# 3_EVB-A32S1-M_Motor.net
KiCad netlist of a schematic drawn in Altium Designer
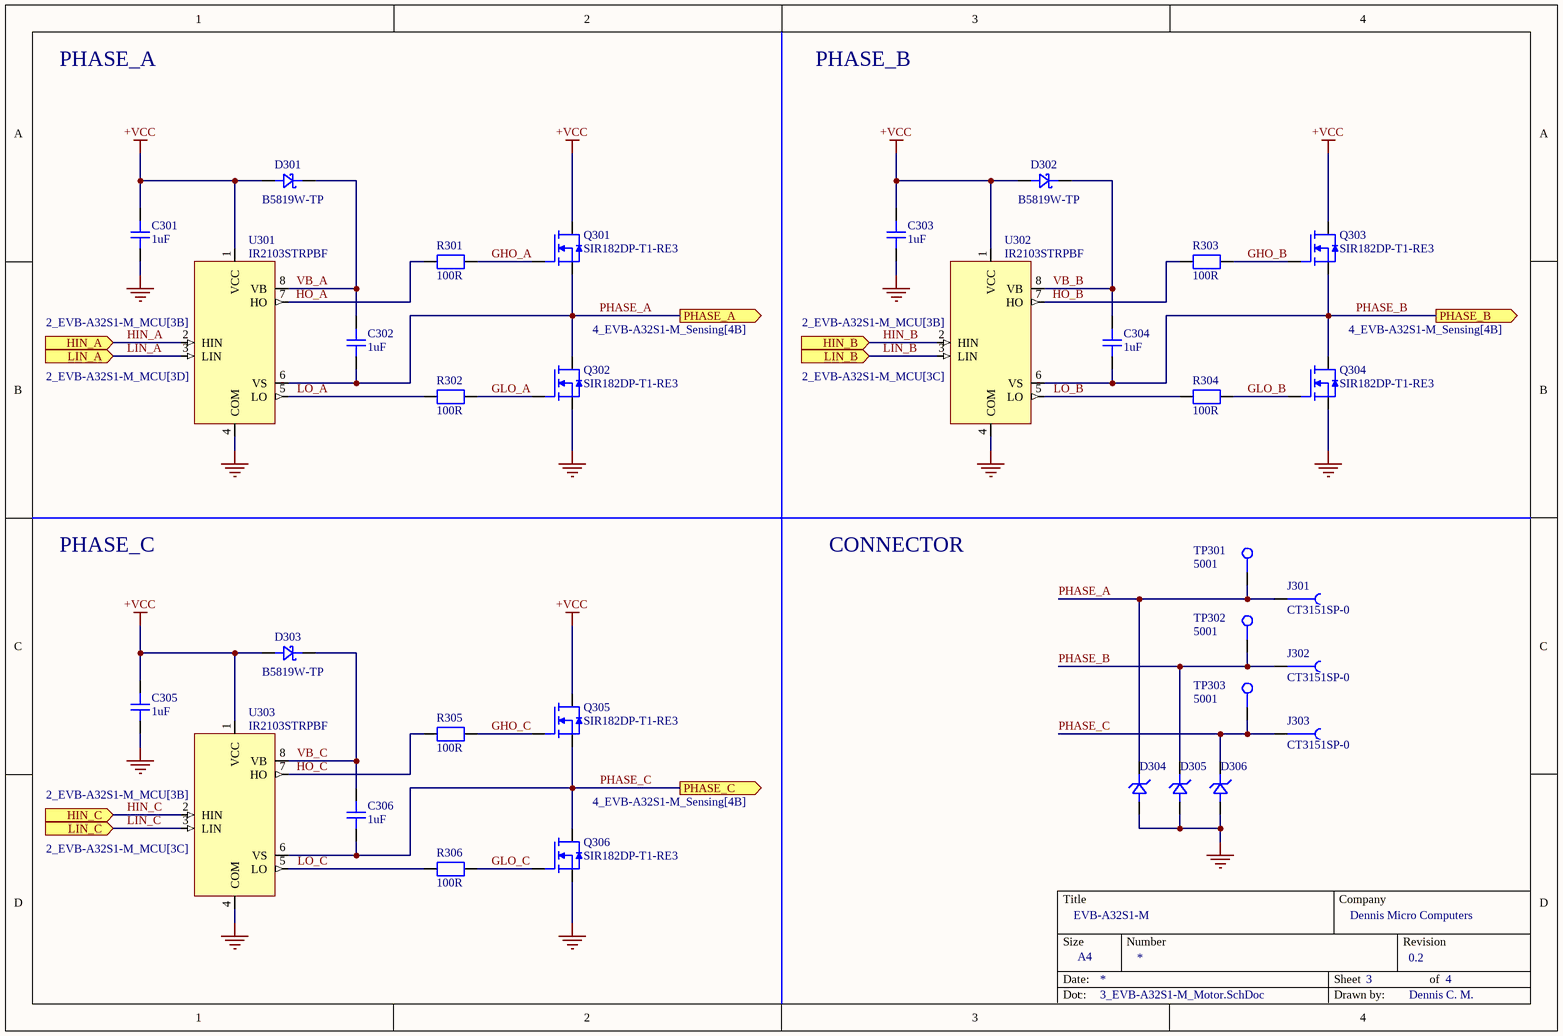
[diagram p0: 3_EVB-A32S1-M_Motor.SchDoc]

(export (version "E")
  (design (tool "Eeschema 10.0.6"))
  (components
    (comp (ref "C301")
      (value "1uF")
      (footprint "C_Yageo_CC_0603_A")
      (description "Multilayer Ceramic Capacitor, 1 uF, 16 V, ± 10%, X7R, 0603 [1608 Metric]")
      (fields (field (name "TOLERANCE") "10%") (field (name "VOLTAGE") "16V"))
      (libsource (lib "Dennis Micro Computers") (part "C"))
    )
    (comp (ref "C302")
      (value "1uF")
      (footprint "C_Yageo_CC_0603_A")
      (description "Multilayer Ceramic Capacitor, 1 uF, 16 V, ± 10%, X7R, 0603 [1608 Metric]")
      (fields (field (name "TOLERANCE") "10%") (field (name "VOLTAGE") "16V"))
      (libsource (lib "Dennis Micro Computers") (part "C"))
    )
    (comp (ref "C303")
      (value "1uF")
      (footprint "C_Yageo_CC_0603_A")
      (description "Multilayer Ceramic Capacitor, 1 uF, 16 V, ± 10%, X7R, 0603 [1608 Metric]")
      (fields (field (name "TOLERANCE") "10%") (field (name "VOLTAGE") "16V"))
      (libsource (lib "Dennis Micro Computers") (part "C"))
    )
    (comp (ref "C304")
      (value "1uF")
      (footprint "C_Yageo_CC_0603_A")
      (description "Multilayer Ceramic Capacitor, 1 uF, 16 V, ± 10%, X7R, 0603 [1608 Metric]")
      (fields (field (name "TOLERANCE") "10%") (field (name "VOLTAGE") "16V"))
      (libsource (lib "Dennis Micro Computers") (part "C"))
    )
    (comp (ref "C305")
      (value "1uF")
      (footprint "C_Yageo_CC_0603_A")
      (description "Multilayer Ceramic Capacitor, 1 uF, 16 V, ± 10%, X7R, 0603 [1608 Metric]")
      (fields (field (name "TOLERANCE") "10%") (field (name "VOLTAGE") "16V"))
      (libsource (lib "Dennis Micro Computers") (part "C"))
    )
    (comp (ref "C306")
      (value "1uF")
      (footprint "C_Yageo_CC_0603_A")
      (description "Multilayer Ceramic Capacitor, 1 uF, 16 V, ± 10%, X7R, 0603 [1608 Metric]")
      (fields (field (name "TOLERANCE") "10%") (field (name "VOLTAGE") "16V"))
      (libsource (lib "Dennis Micro Computers") (part "C"))
    )
    (comp (ref "D301")
      (value "B5819W-TP")
      (footprint "D_Schottky_MCC_SOD-123")
      (description "Rectifier Diode, Schottky, 1 Phase, 1 Element, 1A, 40V V(RRM), Silicon")
      (libsource (lib "Dennis Micro Computers") (part "D_Schottky"))
    )
    (comp (ref "D302")
      (value "B5819W-TP")
      (footprint "D_Schottky_MCC_SOD-123")
      (description "Rectifier Diode, Schottky, 1 Phase, 1 Element, 1A, 40V V(RRM), Silicon")
      (libsource (lib "Dennis Micro Computers") (part "D_Schottky"))
    )
    (comp (ref "D303")
      (value "B5819W-TP")
      (footprint "D_Schottky_MCC_SOD-123")
      (description "Rectifier Diode, Schottky, 1 Phase, 1 Element, 1A, 40V V(RRM), Silicon")
      (libsource (lib "Dennis Micro Computers") (part "D_Schottky"))
    )
    (comp (ref "D304")
      (value "SMBJ15A-13-F")
      (footprint "D_TVS_Uni_Diodes_DO-214AA_B")
      (description "TVS Diode Single Uni-Dir 15V 600W 2-Pin SMB T/R / TVS DIODE 15VWM 24.4VC SMB")
      (libsource (lib "Dennis Micro Computers") (part "D_TVS_Uni"))
    )
    (comp (ref "D305")
      (value "SMBJ15A-13-F")
      (footprint "D_TVS_Uni_Diodes_DO-214AA_B")
      (description "TVS Diode Single Uni-Dir 15V 600W 2-Pin SMB T/R / TVS DIODE 15VWM 24.4VC SMB")
      (libsource (lib "Dennis Micro Computers") (part "D_TVS_Uni"))
    )
    (comp (ref "D306")
      (value "SMBJ15A-13-F")
      (footprint "D_TVS_Uni_Diodes_DO-214AA_B")
      (description "TVS Diode Single Uni-Dir 15V 600W 2-Pin SMB T/R / TVS DIODE 15VWM 24.4VC SMB")
      (libsource (lib "Dennis Micro Computers") (part "D_TVS_Uni"))
    )
    (comp (ref "J301")
      (value "CT3151SP-0")
      (footprint "J_CalTest_CT3151SP-0")
      (description "Conn 4mm Safety Banana Jack F 1 POS Solder RA Thru-Hole 1 Port Bag")
      (libsource (lib "Dennis Micro Computers") (part "J_01x01_Socket"))
    )
    (comp (ref "J302")
      (value "CT3151SP-0")
      (footprint "J_CalTest_CT3151SP-0")
      (description "Conn 4mm Safety Banana Jack F 1 POS Solder RA Thru-Hole 1 Port Bag")
      (libsource (lib "Dennis Micro Computers") (part "J_01x01_Socket"))
    )
    (comp (ref "J303")
      (value "CT3151SP-0")
      (footprint "J_CalTest_CT3151SP-0")
      (description "Conn 4mm Safety Banana Jack F 1 POS Solder RA Thru-Hole 1 Port Bag")
      (libsource (lib "Dennis Micro Computers") (part "J_01x01_Socket"))
    )
    (comp (ref "Q301")
      (value "SIR182DP-T1-RE3")
      (footprint "Q_Vishay_PowerPACK-SO-8-Single")
      (description "TrenchFET Gen IV Power MOSFET N-Channel Single 60V VDS ±20V VGS 60A ID 8-Pin PowerPAK SOIC T/R")
      (libsource (lib "Dennis Micro Computers") (part "Q_NMOS"))
    )
    (comp (ref "Q302")
      (value "SIR182DP-T1-RE3")
      (footprint "Q_Vishay_PowerPACK-SO-8-Single")
      (description "TrenchFET Gen IV Power MOSFET N-Channel Single 60V VDS ±20V VGS 60A ID 8-Pin PowerPAK SOIC T/R")
      (libsource (lib "Dennis Micro Computers") (part "Q_NMOS"))
    )
    (comp (ref "Q303")
      (value "SIR182DP-T1-RE3")
      (footprint "Q_Vishay_PowerPACK-SO-8-Single")
      (description "TrenchFET Gen IV Power MOSFET N-Channel Single 60V VDS ±20V VGS 60A ID 8-Pin PowerPAK SOIC T/R")
      (libsource (lib "Dennis Micro Computers") (part "Q_NMOS"))
    )
    (comp (ref "Q304")
      (value "SIR182DP-T1-RE3")
      (footprint "Q_Vishay_PowerPACK-SO-8-Single")
      (description "TrenchFET Gen IV Power MOSFET N-Channel Single 60V VDS ±20V VGS 60A ID 8-Pin PowerPAK SOIC T/R")
      (libsource (lib "Dennis Micro Computers") (part "Q_NMOS"))
    )
    (comp (ref "Q305")
      (value "SIR182DP-T1-RE3")
      (footprint "Q_Vishay_PowerPACK-SO-8-Single")
      (description "TrenchFET Gen IV Power MOSFET N-Channel Single 60V VDS ±20V VGS 60A ID 8-Pin PowerPAK SOIC T/R")
      (libsource (lib "Dennis Micro Computers") (part "Q_NMOS"))
    )
    (comp (ref "Q306")
      (value "SIR182DP-T1-RE3")
      (footprint "Q_Vishay_PowerPACK-SO-8-Single")
      (description "TrenchFET Gen IV Power MOSFET N-Channel Single 60V VDS ±20V VGS 60A ID 8-Pin PowerPAK SOIC T/R")
      (libsource (lib "Dennis Micro Computers") (part "Q_NMOS"))
    )
    (comp (ref "R301")
      (value "100R")
      (footprint "R_Yageo_RCL_1206_A")
      (description "SMD Chip Resistor, 100 Ohm, ± 1%, 250 mW, 1206 [3216 Metric], Thick Film, General Purpose")
      (fields (field (name "TOLERANCE") "1%") (field (name "Comment") "RC1206FR-07100RL"))
      (libsource (lib "Dennis Micro Computers") (part "R"))
    )
    (comp (ref "R302")
      (value "100R")
      (footprint "R_Yageo_RCL_1206_A")
      (description "SMD Chip Resistor, 100 Ohm, ± 1%, 250 mW, 1206 [3216 Metric], Thick Film, General Purpose")
      (fields (field (name "TOLERANCE") "1%") (field (name "Comment") "RC1206FR-07100RL"))
      (libsource (lib "Dennis Micro Computers") (part "R"))
    )
    (comp (ref "R303")
      (value "100R")
      (footprint "R_Yageo_RCL_1206_A")
      (description "SMD Chip Resistor, 100 Ohm, ± 1%, 250 mW, 1206 [3216 Metric], Thick Film, General Purpose")
      (fields (field (name "TOLERANCE") "1%") (field (name "Comment") "RC1206FR-07100RL"))
      (libsource (lib "Dennis Micro Computers") (part "R"))
    )
    (comp (ref "R304")
      (value "100R")
      (footprint "R_Yageo_RCL_1206_A")
      (description "SMD Chip Resistor, 100 Ohm, ± 1%, 250 mW, 1206 [3216 Metric], Thick Film, General Purpose")
      (fields (field (name "TOLERANCE") "1%") (field (name "Comment") "RC1206FR-07100RL"))
      (libsource (lib "Dennis Micro Computers") (part "R"))
    )
    (comp (ref "R305")
      (value "100R")
      (footprint "R_Yageo_RCL_1206_A")
      (description "SMD Chip Resistor, 100 Ohm, ± 1%, 250 mW, 1206 [3216 Metric], Thick Film, General Purpose")
      (fields (field (name "TOLERANCE") "1%") (field (name "Comment") "RC1206FR-07100RL"))
      (libsource (lib "Dennis Micro Computers") (part "R"))
    )
    (comp (ref "R306")
      (value "100R")
      (footprint "R_Yageo_RCL_1206_A")
      (description "SMD Chip Resistor, 100 Ohm, ± 1%, 250 mW, 1206 [3216 Metric], Thick Film, General Purpose")
      (fields (field (name "TOLERANCE") "1%") (field (name "Comment") "RC1206FR-07100RL"))
      (libsource (lib "Dennis Micro Computers") (part "R"))
    )
    (comp (ref "TP301")
      (value "5001")
      (footprint "TP_Keystone_TH")
      (libsource (lib "Dennis Micro Computers") (part "TP"))
    )
    (comp (ref "TP302")
      (value "5001")
      (footprint "TP_Keystone_TH")
      (libsource (lib "Dennis Micro Computers") (part "TP"))
    )
    (comp (ref "TP303")
      (value "5001")
      (footprint "TP_Keystone_TH")
      (libsource (lib "Dennis Micro Computers") (part "TP"))
    )
    (comp (ref "U301")
      (value "IR2103STRPBF")
      (footprint "U_Infineon_8-SOIC_3.9mm")
      (description "600 V half-bridge gate driver IC with shoot through protection, SOIC 8N, RoHS")
      (libsource (lib "Dennis Micro Computers") (part "U_IR2103STRPBF"))
    )
    (comp (ref "U302")
      (value "IR2103STRPBF")
      (footprint "U_Infineon_8-SOIC_3.9mm")
      (description "600 V half-bridge gate driver IC with shoot through protection, SOIC 8N, RoHS")
      (libsource (lib "Dennis Micro Computers") (part "U_IR2103STRPBF"))
    )
    (comp (ref "U303")
      (value "IR2103STRPBF")
      (footprint "U_Infineon_8-SOIC_3.9mm")
      (description "600 V half-bridge gate driver IC with shoot through protection, SOIC 8N, RoHS")
      (libsource (lib "Dennis Micro Computers") (part "U_IR2103STRPBF"))
    )
  )
  (nets
    (net (code "1") (name "+VCC") (class "Default")
      (node (ref "C301") (pin "2") (pinfunction "2_2") (pintype "passive"))
      (node (ref "C303") (pin "2") (pinfunction "2_2") (pintype "passive"))
      (node (ref "C305") (pin "2") (pinfunction "2_2") (pintype "passive"))
      (node (ref "D301") (pin "2") (pinfunction "2_2") (pintype "passive"))
      (node (ref "D302") (pin "2") (pinfunction "2_2") (pintype "passive"))
      (node (ref "D303") (pin "2") (pinfunction "2_2") (pintype "passive"))
      (node (ref "Q301") (pin "1") (pinfunction "D_1") (pintype "passive"))
      (node (ref "Q303") (pin "1") (pinfunction "D_1") (pintype "passive"))
      (node (ref "Q305") (pin "1") (pinfunction "D_1") (pintype "passive"))
      (node (ref "U301") (pin "1") (pinfunction "VCC_1") (pintype "power_in"))
      (node (ref "U302") (pin "1") (pinfunction "VCC_1") (pintype "power_in"))
      (node (ref "U303") (pin "1") (pinfunction "VCC_1") (pintype "power_in"))
    )
    (net (code "2") (name "/GHO_A") (class "Default")
      (node (ref "Q301") (pin "2") (pinfunction "G_2") (pintype "passive"))
      (node (ref "R301") (pin "2") (pinfunction "2_2") (pintype "passive"))
    )
    (net (code "3") (name "/GHO_B") (class "Default")
      (node (ref "Q303") (pin "2") (pinfunction "G_2") (pintype "passive"))
      (node (ref "R303") (pin "2") (pinfunction "2_2") (pintype "passive"))
    )
    (net (code "4") (name "/GHO_C") (class "Default")
      (node (ref "Q305") (pin "2") (pinfunction "G_2") (pintype "passive"))
      (node (ref "R305") (pin "2") (pinfunction "2_2") (pintype "passive"))
    )
    (net (code "5") (name "/GLO_A") (class "Default")
      (node (ref "Q302") (pin "2") (pinfunction "G_2") (pintype "passive"))
      (node (ref "R302") (pin "2") (pinfunction "2_2") (pintype "passive"))
    )
    (net (code "6") (name "/GLO_B") (class "Default")
      (node (ref "Q304") (pin "2") (pinfunction "G_2") (pintype "passive"))
      (node (ref "R304") (pin "2") (pinfunction "2_2") (pintype "passive"))
    )
    (net (code "7") (name "/GLO_C") (class "Default")
      (node (ref "Q306") (pin "2") (pinfunction "G_2") (pintype "passive"))
      (node (ref "R306") (pin "2") (pinfunction "2_2") (pintype "passive"))
    )
    (net (code "8") (name "/HIN_A") (class "Default")
      (node (ref "U301") (pin "2") (pinfunction "HIN_2") (pintype "input"))
    )
    (net (code "9") (name "/HIN_B") (class "Default")
      (node (ref "U302") (pin "2") (pinfunction "HIN_2") (pintype "input"))
    )
    (net (code "10") (name "/HIN_C") (class "Default")
      (node (ref "U303") (pin "2") (pinfunction "HIN_2") (pintype "input"))
    )
    (net (code "11") (name "/HO_A") (class "Default")
      (node (ref "R301") (pin "1") (pinfunction "1_1") (pintype "passive"))
      (node (ref "U301") (pin "7") (pinfunction "HO_7") (pintype "output"))
    )
    (net (code "12") (name "/HO_B") (class "Default")
      (node (ref "R303") (pin "1") (pinfunction "1_1") (pintype "passive"))
      (node (ref "U302") (pin "7") (pinfunction "HO_7") (pintype "output"))
    )
    (net (code "13") (name "/HO_C") (class "Default")
      (node (ref "R305") (pin "1") (pinfunction "1_1") (pintype "passive"))
      (node (ref "U303") (pin "7") (pinfunction "HO_7") (pintype "output"))
    )
    (net (code "14") (name "/LIN_A") (class "Default")
      (node (ref "U301") (pin "3") (pinfunction "LIN_3") (pintype "input"))
    )
    (net (code "15") (name "/LIN_B") (class "Default")
      (node (ref "U302") (pin "3") (pinfunction "LIN_3") (pintype "input"))
    )
    (net (code "16") (name "/LIN_C") (class "Default")
      (node (ref "U303") (pin "3") (pinfunction "LIN_3") (pintype "input"))
    )
    (net (code "17") (name "/LO_A") (class "Default")
      (node (ref "R302") (pin "1") (pinfunction "1_1") (pintype "passive"))
      (node (ref "U301") (pin "5") (pinfunction "LO_5") (pintype "output"))
    )
    (net (code "18") (name "/LO_B") (class "Default")
      (node (ref "R304") (pin "1") (pinfunction "1_1") (pintype "passive"))
      (node (ref "U302") (pin "5") (pinfunction "LO_5") (pintype "output"))
    )
    (net (code "19") (name "/LO_C") (class "Default")
      (node (ref "R306") (pin "1") (pinfunction "1_1") (pintype "passive"))
      (node (ref "U303") (pin "5") (pinfunction "LO_5") (pintype "output"))
    )
    (net (code "20") (name "/PHASE_A") (class "Default")
      (node (ref "C302") (pin "1") (pinfunction "1_1") (pintype "passive"))
      (node (ref "D304") (pin "1") (pinfunction "1_1") (pintype "passive"))
      (node (ref "J301") (pin "1") (pinfunction "1_1") (pintype "passive"))
      (node (ref "Q301") (pin "3") (pinfunction "S_3") (pintype "passive"))
      (node (ref "Q302") (pin "1") (pinfunction "D_1") (pintype "passive"))
      (node (ref "TP301") (pin "1") (pinfunction "1_1") (pintype "passive"))
      (node (ref "U301") (pin "6") (pinfunction "VS_6") (pintype "passive"))
    )
    (net (code "21") (name "/PHASE_B") (class "Default")
      (node (ref "C304") (pin "1") (pinfunction "1_1") (pintype "passive"))
      (node (ref "D305") (pin "1") (pinfunction "1_1") (pintype "passive"))
      (node (ref "J302") (pin "1") (pinfunction "1_1") (pintype "passive"))
      (node (ref "Q303") (pin "3") (pinfunction "S_3") (pintype "passive"))
      (node (ref "Q304") (pin "1") (pinfunction "D_1") (pintype "passive"))
      (node (ref "TP302") (pin "1") (pinfunction "1_1") (pintype "passive"))
      (node (ref "U302") (pin "6") (pinfunction "VS_6") (pintype "passive"))
    )
    (net (code "22") (name "/PHASE_C") (class "Default")
      (node (ref "C306") (pin "1") (pinfunction "1_1") (pintype "passive"))
      (node (ref "D306") (pin "1") (pinfunction "1_1") (pintype "passive"))
      (node (ref "J303") (pin "1") (pinfunction "1_1") (pintype "passive"))
      (node (ref "Q305") (pin "3") (pinfunction "S_3") (pintype "passive"))
      (node (ref "Q306") (pin "1") (pinfunction "D_1") (pintype "passive"))
      (node (ref "TP303") (pin "1") (pinfunction "1_1") (pintype "passive"))
      (node (ref "U303") (pin "6") (pinfunction "VS_6") (pintype "passive"))
    )
    (net (code "23") (name "/VB_A") (class "Default")
      (node (ref "C302") (pin "2") (pinfunction "2_2") (pintype "passive"))
      (node (ref "D301") (pin "1") (pinfunction "1_1") (pintype "passive"))
      (node (ref "U301") (pin "8") (pinfunction "VB_8") (pintype "passive"))
    )
    (net (code "24") (name "/VB_B") (class "Default")
      (node (ref "C304") (pin "2") (pinfunction "2_2") (pintype "passive"))
      (node (ref "D302") (pin "1") (pinfunction "1_1") (pintype "passive"))
      (node (ref "U302") (pin "8") (pinfunction "VB_8") (pintype "passive"))
    )
    (net (code "25") (name "/VB_C") (class "Default")
      (node (ref "C306") (pin "2") (pinfunction "2_2") (pintype "passive"))
      (node (ref "D303") (pin "1") (pinfunction "1_1") (pintype "passive"))
      (node (ref "U303") (pin "8") (pinfunction "VB_8") (pintype "passive"))
    )
    (net (code "26") (name "GND") (class "Default")
      (node (ref "C301") (pin "1") (pinfunction "1_1") (pintype "passive"))
      (node (ref "C303") (pin "1") (pinfunction "1_1") (pintype "passive"))
      (node (ref "C305") (pin "1") (pinfunction "1_1") (pintype "passive"))
      (node (ref "D304") (pin "2") (pinfunction "2_2") (pintype "passive"))
      (node (ref "D305") (pin "2") (pinfunction "2_2") (pintype "passive"))
      (node (ref "D306") (pin "2") (pinfunction "2_2") (pintype "passive"))
      (node (ref "Q302") (pin "3") (pinfunction "S_3") (pintype "passive"))
      (node (ref "Q304") (pin "3") (pinfunction "S_3") (pintype "passive"))
      (node (ref "Q306") (pin "3") (pinfunction "S_3") (pintype "passive"))
      (node (ref "U301") (pin "4") (pinfunction "COM_4") (pintype "passive"))
      (node (ref "U302") (pin "4") (pinfunction "COM_4") (pintype "passive"))
      (node (ref "U303") (pin "4") (pinfunction "COM_4") (pintype "passive"))
    )
  )
)
